# tinynumitronboard-extended_iv6.net
KiCad netlist of a schematic drawn in EAGLE
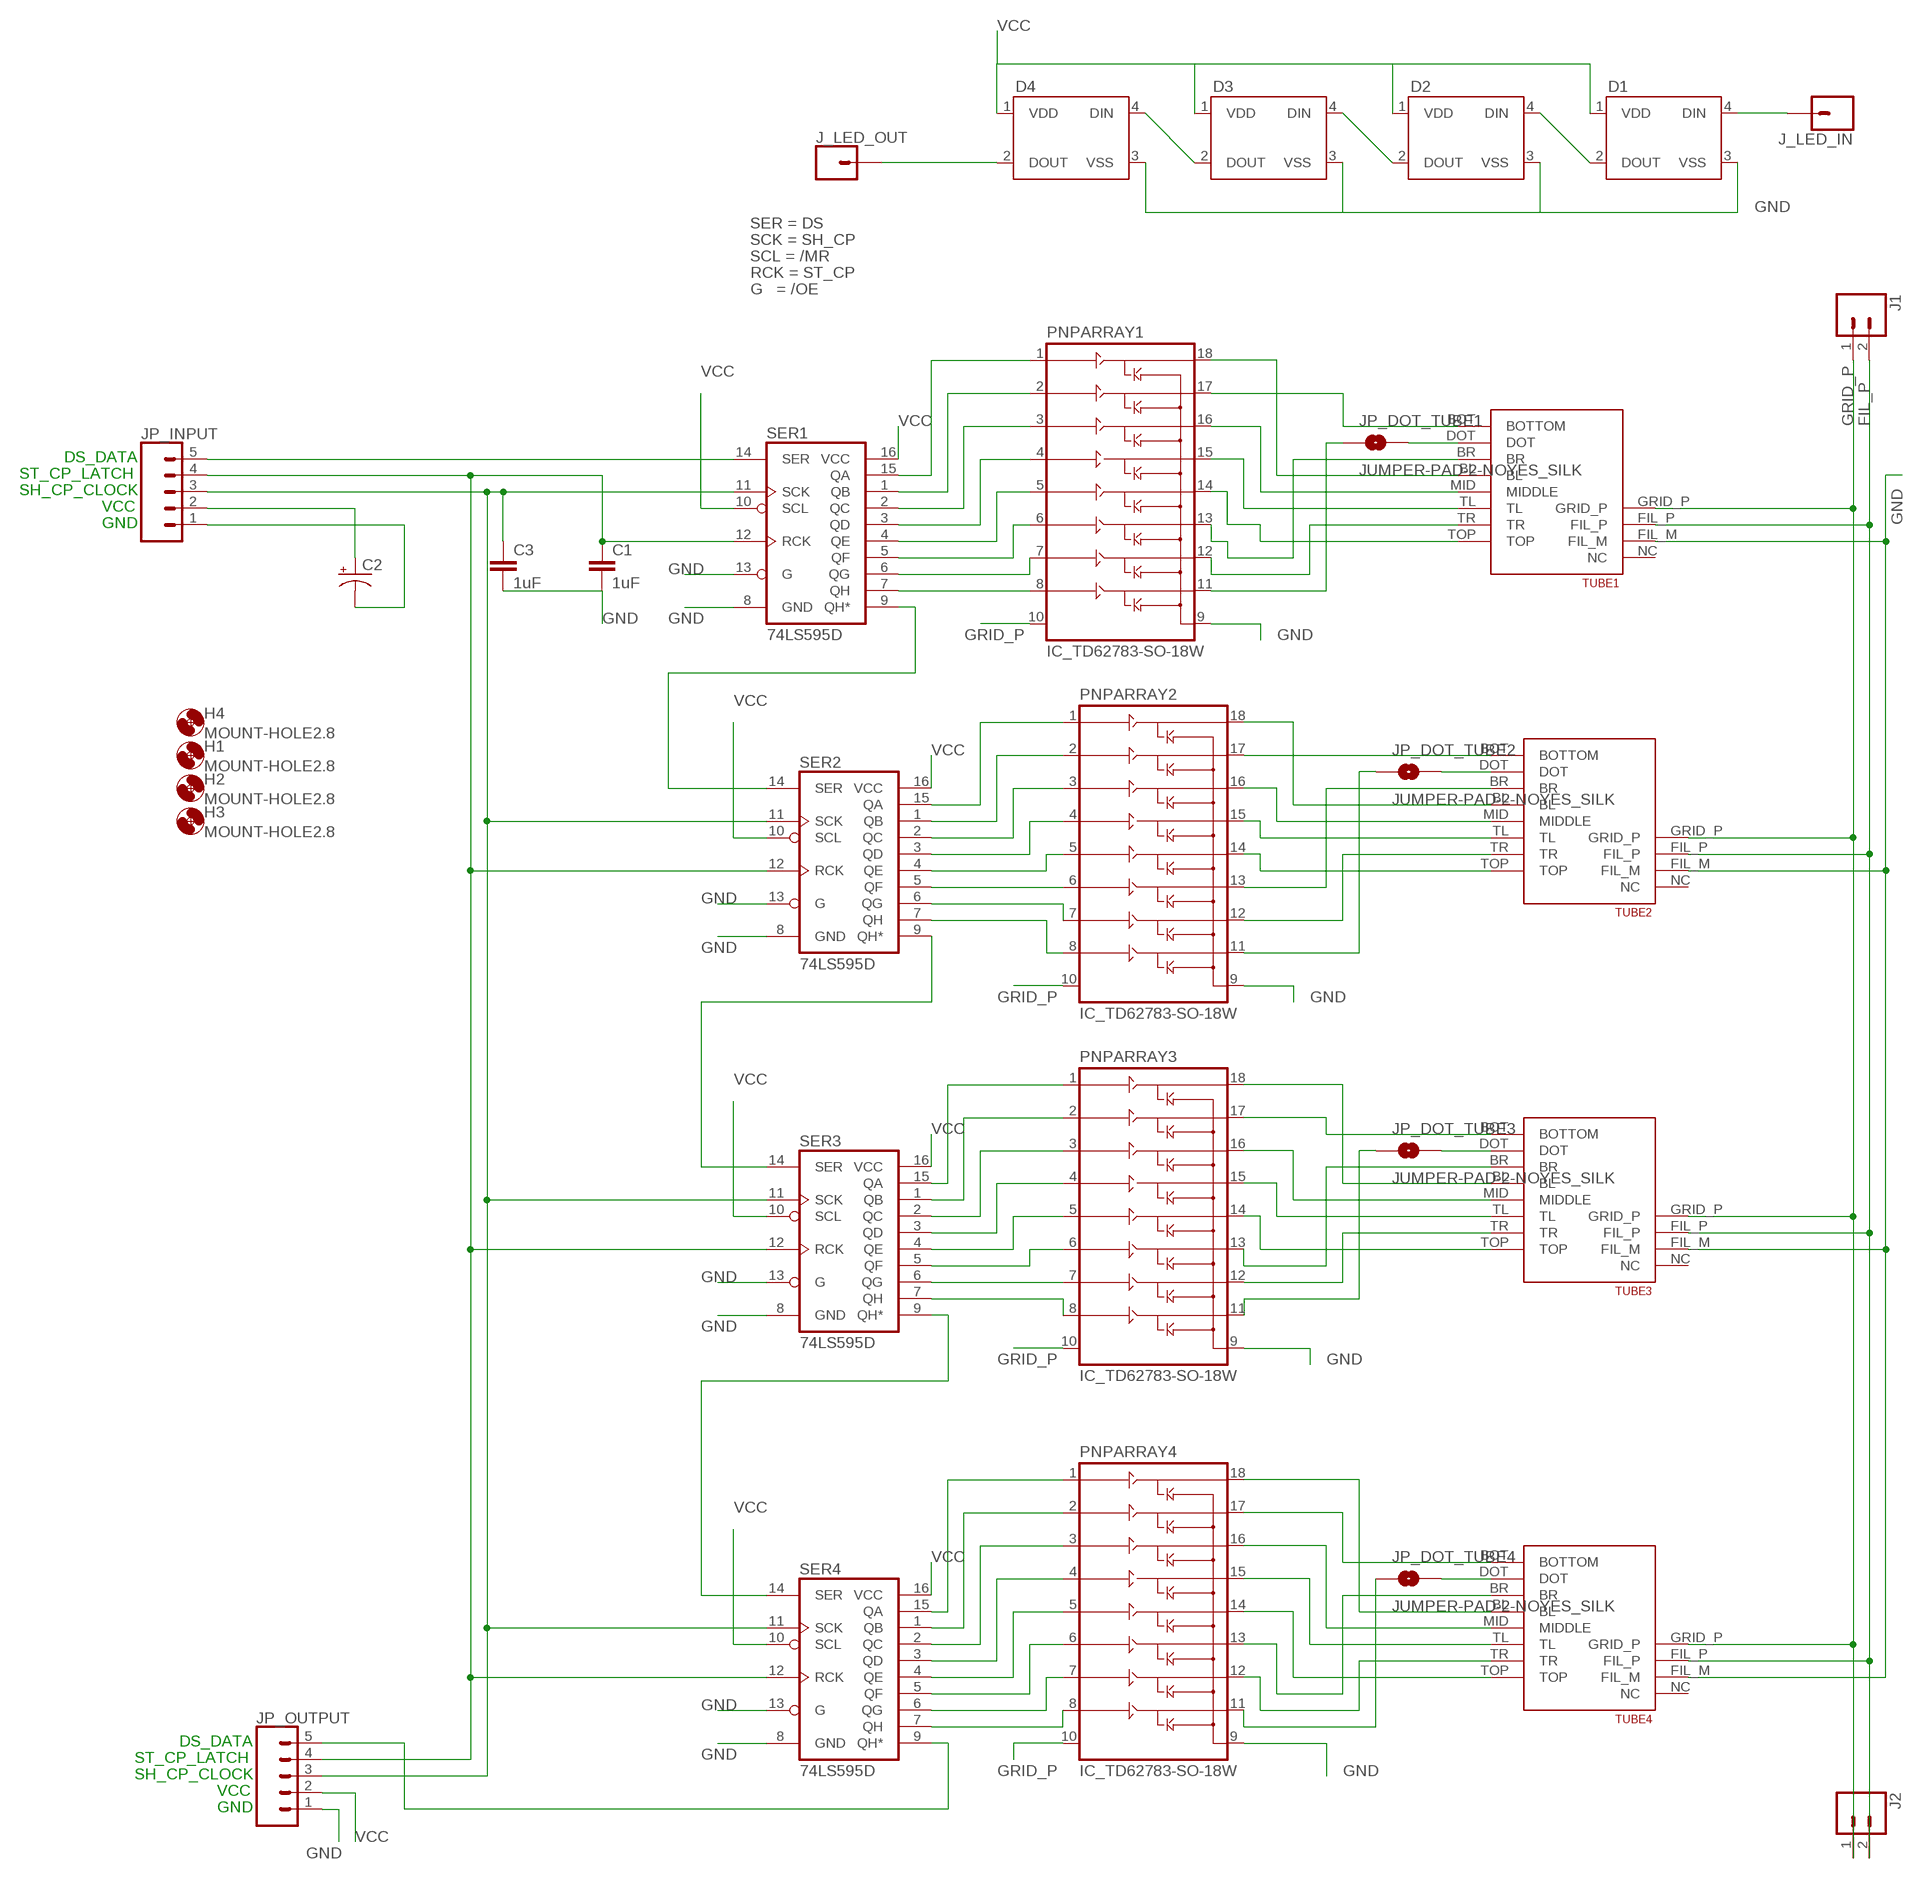
[diagram p0: schematic, sheet 1]

(export (version "E")
  (design (tool "Eeschema 10.0.6"))
  (components
    (comp (ref "C1")
      (value "1uF")
      (footprint "eagle-import:C1206")
      (libsource (lib "eagle-import") (part "C-EUC1206"))
    )
    (comp (ref "C2")
      (value "CAP_POLD")
      (footprint "eagle-import:PANASONIC_D")
      (libsource (lib "eagle-import") (part "CAP_POLD"))
    )
    (comp (ref "C3")
      (value "1uF")
      (footprint "eagle-import:C1206")
      (libsource (lib "eagle-import") (part "C-EUC1206"))
    )
    (comp (ref "D1")
      (value "WS2812B")
      (footprint "eagle-import:WS2812B")
      (libsource (lib "eagle-import") (part "WS2812B"))
    )
    (comp (ref "D2")
      (value "WS2812B")
      (footprint "eagle-import:WS2812B")
      (libsource (lib "eagle-import") (part "WS2812B"))
    )
    (comp (ref "D3")
      (value "WS2812B")
      (footprint "eagle-import:WS2812B")
      (libsource (lib "eagle-import") (part "WS2812B"))
    )
    (comp (ref "D4")
      (value "WS2812B")
      (footprint "eagle-import:WS2812B")
      (libsource (lib "eagle-import") (part "WS2812B"))
    )
    (comp (ref "H1")
      (value "MOUNT-HOLE2.8")
      (footprint "eagle-import:2,8")
      (libsource (lib "eagle-import") (part "MOUNT-HOLE2.8"))
    )
    (comp (ref "H2")
      (value "MOUNT-HOLE2.8")
      (footprint "eagle-import:2,8")
      (libsource (lib "eagle-import") (part "MOUNT-HOLE2.8"))
    )
    (comp (ref "H3")
      (value "MOUNT-HOLE2.8")
      (footprint "eagle-import:2,8")
      (libsource (lib "eagle-import") (part "MOUNT-HOLE2.8"))
    )
    (comp (ref "H4")
      (value "MOUNT-HOLE2.8")
      (footprint "eagle-import:2,8")
      (libsource (lib "eagle-import") (part "MOUNT-HOLE2.8"))
    )
    (comp (ref "J1")
      (value "CONN_021X02_NO_SILK")
      (footprint "eagle-import:1X02_NO_SILK")
      (libsource (lib "eagle-import") (part "CONN_021X02_NO_SILK"))
    )
    (comp (ref "J2")
      (value "CONN_021X02_NO_SILK")
      (footprint "eagle-import:1X02_NO_SILK")
      (libsource (lib "eagle-import") (part "CONN_021X02_NO_SILK"))
    )
    (comp (ref "JP_DOT_TUBE1")
      (value "JUMPER-PAD-2-NOYES_SILK")
      (footprint "eagle-import:PAD-JUMPER-2-NO_YES_SILK")
      (libsource (lib "eagle-import") (part "JUMPER-PAD-2-NOYES_SILK"))
    )
    (comp (ref "JP_DOT_TUBE2")
      (value "JUMPER-PAD-2-NOYES_SILK")
      (footprint "eagle-import:PAD-JUMPER-2-NO_YES_SILK")
      (libsource (lib "eagle-import") (part "JUMPER-PAD-2-NOYES_SILK"))
    )
    (comp (ref "JP_DOT_TUBE3")
      (value "JUMPER-PAD-2-NOYES_SILK")
      (footprint "eagle-import:PAD-JUMPER-2-NO_YES_SILK")
      (libsource (lib "eagle-import") (part "JUMPER-PAD-2-NOYES_SILK"))
    )
    (comp (ref "JP_DOT_TUBE4")
      (value "JUMPER-PAD-2-NOYES_SILK")
      (footprint "eagle-import:PAD-JUMPER-2-NO_YES_SILK")
      (libsource (lib "eagle-import") (part "JUMPER-PAD-2-NOYES_SILK"))
    )
    (comp (ref "JP_INPUT")
      (value "CONN_05NO_SILK")
      (footprint "eagle-import:1X05_NO_SILK")
      (libsource (lib "eagle-import") (part "CONN_05NO_SILK"))
    )
    (comp (ref "JP_OUTPUT")
      (value "CONN_05NO_SILK")
      (footprint "eagle-import:1X05_NO_SILK")
      (libsource (lib "eagle-import") (part "CONN_05NO_SILK"))
    )
    (comp (ref "J_LED_IN")
      (value "CONN_01")
      (footprint "eagle-import:1X01")
      (libsource (lib "eagle-import") (part "CONN_01"))
    )
    (comp (ref "J_LED_OUT")
      (value "CONN_01")
      (footprint "eagle-import:1X01")
      (libsource (lib "eagle-import") (part "CONN_01"))
    )
    (comp (ref "PNPARRAY1")
      (value "IC_TD62783-SO-18W")
      (footprint "eagle-import:SO-18L")
      (libsource (lib "eagle-import") (part "IC_TD62783-SO-18W"))
    )
    (comp (ref "PNPARRAY2")
      (value "IC_TD62783-SO-18W")
      (footprint "eagle-import:SO-18L")
      (libsource (lib "eagle-import") (part "IC_TD62783-SO-18W"))
    )
    (comp (ref "PNPARRAY3")
      (value "IC_TD62783-SO-18W")
      (footprint "eagle-import:SO-18L")
      (libsource (lib "eagle-import") (part "IC_TD62783-SO-18W"))
    )
    (comp (ref "PNPARRAY4")
      (value "IC_TD62783-SO-18W")
      (footprint "eagle-import:SO-18L")
      (libsource (lib "eagle-import") (part "IC_TD62783-SO-18W"))
    )
    (comp (ref "SER1")
      (value "74LS595D")
      (footprint "eagle-import:SO16")
      (libsource (lib "eagle-import") (part "74595DLS"))
    )
    (comp (ref "SER2")
      (value "74LS595D")
      (footprint "eagle-import:SO16")
      (libsource (lib "eagle-import") (part "74595DLS"))
    )
    (comp (ref "SER3")
      (value "74LS595D")
      (footprint "eagle-import:SO16")
      (libsource (lib "eagle-import") (part "74595DLS"))
    )
    (comp (ref "SER4")
      (value "74LS595D")
      (footprint "eagle-import:SO16")
      (libsource (lib "eagle-import") (part "74595DLS"))
    )
    (comp (ref "TUBE1")
      (value "IV6_NUMITRONLARGE")
      (footprint "eagle-import:IV6_NUMITRON_PAC_LARGE")
      (libsource (lib "eagle-import") (part "IV6_NUMITRONLARGE"))
    )
    (comp (ref "TUBE2")
      (value "IV6_NUMITRONLARGE")
      (footprint "eagle-import:IV6_NUMITRON_PAC_LARGE")
      (libsource (lib "eagle-import") (part "IV6_NUMITRONLARGE"))
    )
    (comp (ref "TUBE3")
      (value "IV6_NUMITRONLARGE")
      (footprint "eagle-import:IV6_NUMITRON_PAC_LARGE")
      (libsource (lib "eagle-import") (part "IV6_NUMITRONLARGE"))
    )
    (comp (ref "TUBE4")
      (value "IV6_NUMITRONLARGE")
      (footprint "eagle-import:IV6_NUMITRON_PAC_LARGE")
      (libsource (lib "eagle-import") (part "IV6_NUMITRONLARGE"))
    )
  )
  (nets
    (net (code "1") (name "/FIL_P") (class "Default")
      (node (ref "J1") (pin "2") (pinfunction "2_2") (pintype "passive"))
      (node (ref "J2") (pin "2") (pinfunction "2_2") (pintype "passive"))
      (node (ref "TUBE1") (pin "FIL_P") (pinfunction "FIL_P_FIL_P") (pintype "bidirectional"))
      (node (ref "TUBE2") (pin "FIL_P") (pinfunction "FIL_P_FIL_P") (pintype "bidirectional"))
      (node (ref "TUBE3") (pin "FIL_P") (pinfunction "FIL_P_FIL_P") (pintype "bidirectional"))
      (node (ref "TUBE4") (pin "FIL_P") (pinfunction "FIL_P_FIL_P") (pintype "bidirectional"))
    )
    (net (code "2") (name "/GND") (class "Default")
      (node (ref "C1") (pin "2") (pinfunction "2_2") (pintype "passive"))
      (node (ref "C2") (pin "-") (pinfunction "-_-") (pintype "passive"))
      (node (ref "C3") (pin "2") (pinfunction "2_2") (pintype "passive"))
      (node (ref "D1") (pin "3") (pinfunction "VSS_3") (pintype "power_in"))
      (node (ref "D2") (pin "3") (pinfunction "VSS_3") (pintype "power_in"))
      (node (ref "D3") (pin "3") (pinfunction "VSS_3") (pintype "power_in"))
      (node (ref "D4") (pin "3") (pinfunction "VSS_3") (pintype "power_in"))
      (node (ref "JP_INPUT") (pin "1") (pinfunction "1_1") (pintype "passive"))
      (node (ref "JP_OUTPUT") (pin "1") (pinfunction "1_1") (pintype "passive"))
      (node (ref "PNPARRAY1") (pin "9") (pinfunction "GND_9") (pintype "power_in"))
      (node (ref "PNPARRAY2") (pin "9") (pinfunction "GND_9") (pintype "power_in"))
      (node (ref "PNPARRAY3") (pin "9") (pinfunction "GND_9") (pintype "power_in"))
      (node (ref "PNPARRAY4") (pin "9") (pinfunction "GND_9") (pintype "power_in"))
      (node (ref "SER1") (pin "13") (pinfunction "G_13") (pintype "input"))
      (node (ref "SER1") (pin "8") (pinfunction "GND_8") (pintype "power_in"))
      (node (ref "SER2") (pin "13") (pinfunction "G_13") (pintype "input"))
      (node (ref "SER2") (pin "8") (pinfunction "GND_8") (pintype "power_in"))
      (node (ref "SER3") (pin "13") (pinfunction "G_13") (pintype "input"))
      (node (ref "SER3") (pin "8") (pinfunction "GND_8") (pintype "power_in"))
      (node (ref "SER4") (pin "13") (pinfunction "G_13") (pintype "input"))
      (node (ref "SER4") (pin "8") (pinfunction "GND_8") (pintype "power_in"))
      (node (ref "TUBE1") (pin "FIL_M") (pinfunction "FIL_M_FIL_M") (pintype "bidirectional"))
      (node (ref "TUBE2") (pin "FIL_M") (pinfunction "FIL_M_FIL_M") (pintype "bidirectional"))
      (node (ref "TUBE3") (pin "FIL_M") (pinfunction "FIL_M_FIL_M") (pintype "bidirectional"))
      (node (ref "TUBE4") (pin "FIL_M") (pinfunction "FIL_M_FIL_M") (pintype "bidirectional"))
    )
    (net (code "3") (name "/GRID_P") (class "Default")
      (node (ref "J1") (pin "1") (pinfunction "1_1") (pintype "passive"))
      (node (ref "J2") (pin "1") (pinfunction "1_1") (pintype "passive"))
      (node (ref "PNPARRAY1") (pin "10") (pinfunction "VS_10") (pintype "power_in"))
      (node (ref "PNPARRAY2") (pin "10") (pinfunction "VS_10") (pintype "power_in"))
      (node (ref "PNPARRAY3") (pin "10") (pinfunction "VS_10") (pintype "power_in"))
      (node (ref "PNPARRAY4") (pin "10") (pinfunction "VS_10") (pintype "power_in"))
      (node (ref "TUBE1") (pin "GRID_P") (pinfunction "GRID_P_GRID_P") (pintype "bidirectional"))
      (node (ref "TUBE2") (pin "GRID_P") (pinfunction "GRID_P_GRID_P") (pintype "bidirectional"))
      (node (ref "TUBE3") (pin "GRID_P") (pinfunction "GRID_P_GRID_P") (pintype "bidirectional"))
      (node (ref "TUBE4") (pin "GRID_P") (pinfunction "GRID_P_GRID_P") (pintype "bidirectional"))
    )
    (net (code "4") (name "/VCC") (class "Default")
      (node (ref "C2") (pin "+") (pinfunction "+_+") (pintype "passive"))
      (node (ref "D1") (pin "1") (pinfunction "VDD_1") (pintype "power_in"))
      (node (ref "D2") (pin "1") (pinfunction "VDD_1") (pintype "power_in"))
      (node (ref "D3") (pin "1") (pinfunction "VDD_1") (pintype "power_in"))
      (node (ref "D4") (pin "1") (pinfunction "VDD_1") (pintype "power_in"))
      (node (ref "JP_INPUT") (pin "2") (pinfunction "2_2") (pintype "passive"))
      (node (ref "JP_OUTPUT") (pin "2") (pinfunction "2_2") (pintype "passive"))
      (node (ref "SER1") (pin "10") (pinfunction "SCL_10") (pintype "input"))
      (node (ref "SER1") (pin "16") (pinfunction "VCC_16") (pintype "power_in"))
      (node (ref "SER2") (pin "10") (pinfunction "SCL_10") (pintype "input"))
      (node (ref "SER2") (pin "16") (pinfunction "VCC_16") (pintype "power_in"))
      (node (ref "SER3") (pin "10") (pinfunction "SCL_10") (pintype "input"))
      (node (ref "SER3") (pin "16") (pinfunction "VCC_16") (pintype "power_in"))
      (node (ref "SER4") (pin "10") (pinfunction "SCL_10") (pintype "input"))
      (node (ref "SER4") (pin "16") (pinfunction "VCC_16") (pintype "power_in"))
    )
    (net (code "5") (name "Net-(D1-DIN)") (class "Default")
      (node (ref "D1") (pin "4") (pinfunction "DIN_4") (pintype "input"))
      (node (ref "J_LED_IN") (pin "1") (pinfunction "1_1") (pintype "passive"))
    )
    (net (code "6") (name "Net-(D1-DOUT)") (class "Default")
      (node (ref "D1") (pin "2") (pinfunction "DOUT_2") (pintype "output"))
      (node (ref "D2") (pin "4") (pinfunction "DIN_4") (pintype "input"))
    )
    (net (code "7") (name "Net-(D2-DOUT)") (class "Default")
      (node (ref "D2") (pin "2") (pinfunction "DOUT_2") (pintype "output"))
      (node (ref "D3") (pin "4") (pinfunction "DIN_4") (pintype "input"))
    )
    (net (code "8") (name "Net-(D3-DOUT)") (class "Default")
      (node (ref "D3") (pin "2") (pinfunction "DOUT_2") (pintype "output"))
      (node (ref "D4") (pin "4") (pinfunction "DIN_4") (pintype "input"))
    )
    (net (code "9") (name "Net-(D4-DOUT)") (class "Default")
      (node (ref "D4") (pin "2") (pinfunction "DOUT_2") (pintype "output"))
      (node (ref "J_LED_OUT") (pin "1") (pinfunction "1_1") (pintype "passive"))
    )
    (net (code "10") (name "Net-(JP_DOT_TUBE1-Pad2)") (class "Default")
      (node (ref "JP_DOT_TUBE1") (pin "2") (pinfunction "2_2") (pintype "passive"))
      (node (ref "TUBE1") (pin "DOT") (pinfunction "DOT_DOT") (pintype "bidirectional"))
    )
    (net (code "11") (name "Net-(JP_DOT_TUBE2-Pad2)") (class "Default")
      (node (ref "JP_DOT_TUBE2") (pin "2") (pinfunction "2_2") (pintype "passive"))
      (node (ref "TUBE2") (pin "DOT") (pinfunction "DOT_DOT") (pintype "bidirectional"))
    )
    (net (code "12") (name "Net-(JP_DOT_TUBE3-Pad2)") (class "Default")
      (node (ref "JP_DOT_TUBE3") (pin "2") (pinfunction "2_2") (pintype "passive"))
      (node (ref "TUBE3") (pin "DOT") (pinfunction "DOT_DOT") (pintype "bidirectional"))
    )
    (net (code "13") (name "Net-(JP_DOT_TUBE4-Pad2)") (class "Default")
      (node (ref "JP_DOT_TUBE4") (pin "2") (pinfunction "2_2") (pintype "passive"))
      (node (ref "TUBE4") (pin "DOT") (pinfunction "DOT_DOT") (pintype "bidirectional"))
    )
    (net (code "14") (name "Net-(PNPARRAY1-IN1)") (class "Default")
      (node (ref "PNPARRAY1") (pin "1") (pinfunction "IN1_1") (pintype "input"))
      (node (ref "SER1") (pin "15") (pinfunction "QA_15") (pintype "tri_state"))
    )
    (net (code "15") (name "Net-(PNPARRAY1-IN2)") (class "Default")
      (node (ref "PNPARRAY1") (pin "2") (pinfunction "IN2_2") (pintype "input"))
      (node (ref "SER1") (pin "1") (pinfunction "QB_1") (pintype "tri_state"))
    )
    (net (code "16") (name "Net-(PNPARRAY1-IN3)") (class "Default")
      (node (ref "PNPARRAY1") (pin "3") (pinfunction "IN3_3") (pintype "input"))
      (node (ref "SER1") (pin "2") (pinfunction "QC_2") (pintype "tri_state"))
    )
    (net (code "17") (name "Net-(PNPARRAY1-IN4)") (class "Default")
      (node (ref "PNPARRAY1") (pin "4") (pinfunction "IN4_4") (pintype "input"))
      (node (ref "SER1") (pin "3") (pinfunction "QD_3") (pintype "tri_state"))
    )
    (net (code "18") (name "Net-(PNPARRAY1-IN5)") (class "Default")
      (node (ref "PNPARRAY1") (pin "5") (pinfunction "IN5_5") (pintype "input"))
      (node (ref "SER1") (pin "4") (pinfunction "QE_4") (pintype "tri_state"))
    )
    (net (code "19") (name "Net-(PNPARRAY1-IN6)") (class "Default")
      (node (ref "PNPARRAY1") (pin "6") (pinfunction "IN6_6") (pintype "input"))
      (node (ref "SER1") (pin "5") (pinfunction "QF_5") (pintype "tri_state"))
    )
    (net (code "20") (name "Net-(PNPARRAY1-IN7)") (class "Default")
      (node (ref "PNPARRAY1") (pin "7") (pinfunction "IN7_7") (pintype "input"))
      (node (ref "SER1") (pin "6") (pinfunction "QG_6") (pintype "tri_state"))
    )
    (net (code "21") (name "Net-(PNPARRAY1-IN8)") (class "Default")
      (node (ref "PNPARRAY1") (pin "8") (pinfunction "IN8_8") (pintype "input"))
      (node (ref "SER1") (pin "7") (pinfunction "QH_7") (pintype "tri_state"))
    )
    (net (code "22") (name "Net-(PNPARRAY1-OUT1)") (class "Default")
      (node (ref "PNPARRAY1") (pin "18") (pinfunction "OUT1_18") (pintype "output"))
      (node (ref "TUBE1") (pin "BL") (pinfunction "BL_BL") (pintype "bidirectional"))
    )
    (net (code "23") (name "Net-(PNPARRAY1-OUT2)") (class "Default")
      (node (ref "PNPARRAY1") (pin "17") (pinfunction "OUT2_17") (pintype "output"))
      (node (ref "TUBE1") (pin "BOT") (pinfunction "BOTTOM_BOT") (pintype "bidirectional"))
    )
    (net (code "24") (name "Net-(PNPARRAY1-OUT3)") (class "Default")
      (node (ref "PNPARRAY1") (pin "16") (pinfunction "OUT3_16") (pintype "output"))
      (node (ref "TUBE1") (pin "MID") (pinfunction "MIDDLE_MID") (pintype "bidirectional"))
    )
    (net (code "25") (name "Net-(PNPARRAY1-OUT4)") (class "Default")
      (node (ref "PNPARRAY1") (pin "15") (pinfunction "OUT4_15") (pintype "output"))
      (node (ref "TUBE1") (pin "TL") (pinfunction "TL_TL") (pintype "bidirectional"))
    )
    (net (code "26") (name "Net-(PNPARRAY1-OUT5)") (class "Default")
      (node (ref "PNPARRAY1") (pin "14") (pinfunction "OUT5_14") (pintype "output"))
      (node (ref "TUBE1") (pin "TOP") (pinfunction "TOP_TOP") (pintype "bidirectional"))
    )
    (net (code "27") (name "Net-(PNPARRAY1-OUT6)") (class "Default")
      (node (ref "PNPARRAY1") (pin "13") (pinfunction "OUT6_13") (pintype "output"))
      (node (ref "TUBE1") (pin "BR") (pinfunction "BR_BR") (pintype "bidirectional"))
    )
    (net (code "28") (name "Net-(PNPARRAY1-OUT7)") (class "Default")
      (node (ref "PNPARRAY1") (pin "12") (pinfunction "OUT7_12") (pintype "output"))
      (node (ref "TUBE1") (pin "TR") (pinfunction "TR_TR") (pintype "bidirectional"))
    )
    (net (code "29") (name "Net-(PNPARRAY1-OUT8)") (class "Default")
      (node (ref "JP_DOT_TUBE1") (pin "1") (pinfunction "1_1") (pintype "passive"))
      (node (ref "PNPARRAY1") (pin "11") (pinfunction "OUT8_11") (pintype "output"))
    )
    (net (code "30") (name "Net-(PNPARRAY2-IN1)") (class "Default")
      (node (ref "PNPARRAY2") (pin "1") (pinfunction "IN1_1") (pintype "input"))
      (node (ref "SER2") (pin "15") (pinfunction "QA_15") (pintype "tri_state"))
    )
    (net (code "31") (name "Net-(PNPARRAY2-IN2)") (class "Default")
      (node (ref "PNPARRAY2") (pin "2") (pinfunction "IN2_2") (pintype "input"))
      (node (ref "SER2") (pin "1") (pinfunction "QB_1") (pintype "tri_state"))
    )
    (net (code "32") (name "Net-(PNPARRAY2-IN3)") (class "Default")
      (node (ref "PNPARRAY2") (pin "3") (pinfunction "IN3_3") (pintype "input"))
      (node (ref "SER2") (pin "2") (pinfunction "QC_2") (pintype "tri_state"))
    )
    (net (code "33") (name "Net-(PNPARRAY2-IN4)") (class "Default")
      (node (ref "PNPARRAY2") (pin "4") (pinfunction "IN4_4") (pintype "input"))
      (node (ref "SER2") (pin "3") (pinfunction "QD_3") (pintype "tri_state"))
    )
    (net (code "34") (name "Net-(PNPARRAY2-IN5)") (class "Default")
      (node (ref "PNPARRAY2") (pin "5") (pinfunction "IN5_5") (pintype "input"))
      (node (ref "SER2") (pin "4") (pinfunction "QE_4") (pintype "tri_state"))
    )
    (net (code "35") (name "Net-(PNPARRAY2-IN6)") (class "Default")
      (node (ref "PNPARRAY2") (pin "6") (pinfunction "IN6_6") (pintype "input"))
      (node (ref "SER2") (pin "5") (pinfunction "QF_5") (pintype "tri_state"))
    )
    (net (code "36") (name "Net-(PNPARRAY2-IN7)") (class "Default")
      (node (ref "PNPARRAY2") (pin "7") (pinfunction "IN7_7") (pintype "input"))
      (node (ref "SER2") (pin "6") (pinfunction "QG_6") (pintype "tri_state"))
    )
    (net (code "37") (name "Net-(PNPARRAY2-IN8)") (class "Default")
      (node (ref "PNPARRAY2") (pin "8") (pinfunction "IN8_8") (pintype "input"))
      (node (ref "SER2") (pin "7") (pinfunction "QH_7") (pintype "tri_state"))
    )
    (net (code "38") (name "Net-(PNPARRAY2-OUT1)") (class "Default")
      (node (ref "PNPARRAY2") (pin "18") (pinfunction "OUT1_18") (pintype "output"))
      (node (ref "TUBE2") (pin "BL") (pinfunction "BL_BL") (pintype "bidirectional"))
    )
    (net (code "39") (name "Net-(PNPARRAY2-OUT2)") (class "Default")
      (node (ref "PNPARRAY2") (pin "17") (pinfunction "OUT2_17") (pintype "output"))
      (node (ref "TUBE2") (pin "BOT") (pinfunction "BOTTOM_BOT") (pintype "bidirectional"))
    )
    (net (code "40") (name "Net-(PNPARRAY2-OUT3)") (class "Default")
      (node (ref "PNPARRAY2") (pin "16") (pinfunction "OUT3_16") (pintype "output"))
      (node (ref "TUBE2") (pin "MID") (pinfunction "MIDDLE_MID") (pintype "bidirectional"))
    )
    (net (code "41") (name "Net-(PNPARRAY2-OUT4)") (class "Default")
      (node (ref "PNPARRAY2") (pin "15") (pinfunction "OUT4_15") (pintype "output"))
      (node (ref "TUBE2") (pin "TL") (pinfunction "TL_TL") (pintype "bidirectional"))
    )
    (net (code "42") (name "Net-(PNPARRAY2-OUT5)") (class "Default")
      (node (ref "PNPARRAY2") (pin "14") (pinfunction "OUT5_14") (pintype "output"))
      (node (ref "TUBE2") (pin "TOP") (pinfunction "TOP_TOP") (pintype "bidirectional"))
    )
    (net (code "43") (name "Net-(PNPARRAY2-OUT6)") (class "Default")
      (node (ref "PNPARRAY2") (pin "13") (pinfunction "OUT6_13") (pintype "output"))
      (node (ref "TUBE2") (pin "BR") (pinfunction "BR_BR") (pintype "bidirectional"))
    )
    (net (code "44") (name "Net-(PNPARRAY2-OUT7)") (class "Default")
      (node (ref "PNPARRAY2") (pin "12") (pinfunction "OUT7_12") (pintype "output"))
      (node (ref "TUBE2") (pin "TR") (pinfunction "TR_TR") (pintype "bidirectional"))
    )
    (net (code "45") (name "Net-(PNPARRAY2-OUT8)") (class "Default")
      (node (ref "JP_DOT_TUBE2") (pin "1") (pinfunction "1_1") (pintype "passive"))
      (node (ref "PNPARRAY2") (pin "11") (pinfunction "OUT8_11") (pintype "output"))
    )
    (net (code "46") (name "Net-(PNPARRAY3-IN1)") (class "Default")
      (node (ref "PNPARRAY3") (pin "1") (pinfunction "IN1_1") (pintype "input"))
      (node (ref "SER3") (pin "15") (pinfunction "QA_15") (pintype "tri_state"))
    )
    (net (code "47") (name "Net-(PNPARRAY3-IN2)") (class "Default")
      (node (ref "PNPARRAY3") (pin "2") (pinfunction "IN2_2") (pintype "input"))
      (node (ref "SER3") (pin "1") (pinfunction "QB_1") (pintype "tri_state"))
    )
    (net (code "48") (name "Net-(PNPARRAY3-IN3)") (class "Default")
      (node (ref "PNPARRAY3") (pin "3") (pinfunction "IN3_3") (pintype "input"))
      (node (ref "SER3") (pin "2") (pinfunction "QC_2") (pintype "tri_state"))
    )
    (net (code "49") (name "Net-(PNPARRAY3-IN4)") (class "Default")
      (node (ref "PNPARRAY3") (pin "4") (pinfunction "IN4_4") (pintype "input"))
      (node (ref "SER3") (pin "3") (pinfunction "QD_3") (pintype "tri_state"))
    )
    (net (code "50") (name "Net-(PNPARRAY3-IN5)") (class "Default")
      (node (ref "PNPARRAY3") (pin "5") (pinfunction "IN5_5") (pintype "input"))
      (node (ref "SER3") (pin "4") (pinfunction "QE_4") (pintype "tri_state"))
    )
    (net (code "51") (name "Net-(PNPARRAY3-IN6)") (class "Default")
      (node (ref "PNPARRAY3") (pin "6") (pinfunction "IN6_6") (pintype "input"))
      (node (ref "SER3") (pin "5") (pinfunction "QF_5") (pintype "tri_state"))
    )
    (net (code "52") (name "Net-(PNPARRAY3-IN7)") (class "Default")
      (node (ref "PNPARRAY3") (pin "7") (pinfunction "IN7_7") (pintype "input"))
      (node (ref "SER3") (pin "6") (pinfunction "QG_6") (pintype "tri_state"))
    )
    (net (code "53") (name "Net-(PNPARRAY3-IN8)") (class "Default")
      (node (ref "PNPARRAY3") (pin "8") (pinfunction "IN8_8") (pintype "input"))
      (node (ref "SER3") (pin "7") (pinfunction "QH_7") (pintype "tri_state"))
    )
    (net (code "54") (name "Net-(PNPARRAY3-OUT1)") (class "Default")
      (node (ref "PNPARRAY3") (pin "18") (pinfunction "OUT1_18") (pintype "output"))
      (node (ref "TUBE3") (pin "BL") (pinfunction "BL_BL") (pintype "bidirectional"))
    )
    (net (code "55") (name "Net-(PNPARRAY3-OUT2)") (class "Default")
      (node (ref "PNPARRAY3") (pin "17") (pinfunction "OUT2_17") (pintype "output"))
      (node (ref "TUBE3") (pin "BOT") (pinfunction "BOTTOM_BOT") (pintype "bidirectional"))
    )
    (net (code "56") (name "Net-(PNPARRAY3-OUT3)") (class "Default")
      (node (ref "PNPARRAY3") (pin "16") (pinfunction "OUT3_16") (pintype "output"))
      (node (ref "TUBE3") (pin "MID") (pinfunction "MIDDLE_MID") (pintype "bidirectional"))
    )
    (net (code "57") (name "Net-(PNPARRAY3-OUT4)") (class "Default")
      (node (ref "PNPARRAY3") (pin "15") (pinfunction "OUT4_15") (pintype "output"))
      (node (ref "TUBE3") (pin "TL") (pinfunction "TL_TL") (pintype "bidirectional"))
    )
    (net (code "58") (name "Net-(PNPARRAY3-OUT5)") (class "Default")
      (node (ref "PNPARRAY3") (pin "14") (pinfunction "OUT5_14") (pintype "output"))
      (node (ref "TUBE3") (pin "TOP") (pinfunction "TOP_TOP") (pintype "bidirectional"))
    )
    (net (code "59") (name "Net-(PNPARRAY3-OUT6)") (class "Default")
      (node (ref "PNPARRAY3") (pin "13") (pinfunction "OUT6_13") (pintype "output"))
      (node (ref "TUBE3") (pin "BR") (pinfunction "BR_BR") (pintype "bidirectional"))
    )
    (net (code "60") (name "Net-(PNPARRAY3-OUT7)") (class "Default")
      (node (ref "PNPARRAY3") (pin "12") (pinfunction "OUT7_12") (pintype "output"))
      (node (ref "TUBE3") (pin "TR") (pinfunction "TR_TR") (pintype "bidirectional"))
    )
    (net (code "61") (name "Net-(PNPARRAY3-OUT8)") (class "Default")
      (node (ref "JP_DOT_TUBE3") (pin "1") (pinfunction "1_1") (pintype "passive"))
      (node (ref "PNPARRAY3") (pin "11") (pinfunction "OUT8_11") (pintype "output"))
    )
    (net (code "62") (name "Net-(PNPARRAY4-IN1)") (class "Default")
      (node (ref "PNPARRAY4") (pin "1") (pinfunction "IN1_1") (pintype "input"))
      (node (ref "SER4") (pin "15") (pinfunction "QA_15") (pintype "tri_state"))
    )
    (net (code "63") (name "Net-(PNPARRAY4-IN2)") (class "Default")
      (node (ref "PNPARRAY4") (pin "2") (pinfunction "IN2_2") (pintype "input"))
      (node (ref "SER4") (pin "1") (pinfunction "QB_1") (pintype "tri_state"))
    )
    (net (code "64") (name "Net-(PNPARRAY4-IN3)") (class "Default")
      (node (ref "PNPARRAY4") (pin "3") (pinfunction "IN3_3") (pintype "input"))
      (node (ref "SER4") (pin "2") (pinfunction "QC_2") (pintype "tri_state"))
    )
    (net (code "65") (name "Net-(PNPARRAY4-IN4)") (class "Default")
      (node (ref "PNPARRAY4") (pin "4") (pinfunction "IN4_4") (pintype "input"))
      (node (ref "SER4") (pin "3") (pinfunction "QD_3") (pintype "tri_state"))
    )
    (net (code "66") (name "Net-(PNPARRAY4-IN5)") (class "Default")
      (node (ref "PNPARRAY4") (pin "5") (pinfunction "IN5_5") (pintype "input"))
      (node (ref "SER4") (pin "4") (pinfunction "QE_4") (pintype "tri_state"))
    )
    (net (code "67") (name "Net-(PNPARRAY4-IN6)") (class "Default")
      (node (ref "PNPARRAY4") (pin "6") (pinfunction "IN6_6") (pintype "input"))
      (node (ref "SER4") (pin "5") (pinfunction "QF_5") (pintype "tri_state"))
    )
    (net (code "68") (name "Net-(PNPARRAY4-IN7)") (class "Default")
      (node (ref "PNPARRAY4") (pin "7") (pinfunction "IN7_7") (pintype "input"))
      (node (ref "SER4") (pin "6") (pinfunction "QG_6") (pintype "tri_state"))
    )
    (net (code "69") (name "Net-(PNPARRAY4-IN8)") (class "Default")
      (node (ref "PNPARRAY4") (pin "8") (pinfunction "IN8_8") (pintype "input"))
      (node (ref "SER4") (pin "7") (pinfunction "QH_7") (pintype "tri_state"))
    )
    (net (code "70") (name "Net-(PNPARRAY4-OUT1)") (class "Default")
      (node (ref "PNPARRAY4") (pin "18") (pinfunction "OUT1_18") (pintype "output"))
      (node (ref "TUBE4") (pin "BL") (pinfunction "BL_BL") (pintype "bidirectional"))
    )
    (net (code "71") (name "Net-(PNPARRAY4-OUT2)") (class "Default")
      (node (ref "PNPARRAY4") (pin "17") (pinfunction "OUT2_17") (pintype "output"))
      (node (ref "TUBE4") (pin "BOT") (pinfunction "BOTTOM_BOT") (pintype "bidirectional"))
    )
    (net (code "72") (name "Net-(PNPARRAY4-OUT3)") (class "Default")
      (node (ref "PNPARRAY4") (pin "16") (pinfunction "OUT3_16") (pintype "output"))
      (node (ref "TUBE4") (pin "MID") (pinfunction "MIDDLE_MID") (pintype "bidirectional"))
    )
    (net (code "73") (name "Net-(PNPARRAY4-OUT4)") (class "Default")
      (node (ref "PNPARRAY4") (pin "15") (pinfunction "OUT4_15") (pintype "output"))
      (node (ref "TUBE4") (pin "TL") (pinfunction "TL_TL") (pintype "bidirectional"))
    )
    (net (code "74") (name "Net-(PNPARRAY4-OUT5)") (class "Default")
      (node (ref "PNPARRAY4") (pin "14") (pinfunction "OUT5_14") (pintype "output"))
      (node (ref "TUBE4") (pin "TOP") (pinfunction "TOP_TOP") (pintype "bidirectional"))
    )
    (net (code "75") (name "Net-(PNPARRAY4-OUT6)") (class "Default")
      (node (ref "PNPARRAY4") (pin "13") (pinfunction "OUT6_13") (pintype "output"))
      (node (ref "TUBE4") (pin "BR") (pinfunction "BR_BR") (pintype "bidirectional"))
    )
    (net (code "76") (name "Net-(PNPARRAY4-OUT7)") (class "Default")
      (node (ref "PNPARRAY4") (pin "12") (pinfunction "OUT7_12") (pintype "output"))
      (node (ref "TUBE4") (pin "TR") (pinfunction "TR_TR") (pintype "bidirectional"))
    )
    (net (code "77") (name "Net-(PNPARRAY4-OUT8)") (class "Default")
      (node (ref "JP_DOT_TUBE4") (pin "1") (pinfunction "1_1") (pintype "passive"))
      (node (ref "PNPARRAY4") (pin "11") (pinfunction "OUT8_11") (pintype "output"))
    )
    (net (code "78") (name "Net-(SER1-QH*)") (class "Default")
      (node (ref "SER1") (pin "9") (pinfunction "QH*_9") (pintype "tri_state"))
      (node (ref "SER2") (pin "14") (pinfunction "SER_14") (pintype "input"))
    )
    (net (code "79") (name "Net-(SER1-RCK)") (class "Default")
      (node (ref "C1") (pin "1") (pinfunction "1_1") (pintype "passive"))
      (node (ref "JP_INPUT") (pin "4") (pinfunction "4_4") (pintype "passive"))
      (node (ref "JP_OUTPUT") (pin "4") (pinfunction "4_4") (pintype "passive"))
      (node (ref "SER1") (pin "12") (pinfunction "RCK_12") (pintype "input"))
      (node (ref "SER2") (pin "12") (pinfunction "RCK_12") (pintype "input"))
      (node (ref "SER3") (pin "12") (pinfunction "RCK_12") (pintype "input"))
      (node (ref "SER4") (pin "12") (pinfunction "RCK_12") (pintype "input"))
    )
    (net (code "80") (name "Net-(SER1-SCK)") (class "Default")
      (node (ref "C3") (pin "1") (pinfunction "1_1") (pintype "passive"))
      (node (ref "JP_INPUT") (pin "3") (pinfunction "3_3") (pintype "passive"))
      (node (ref "JP_OUTPUT") (pin "3") (pinfunction "3_3") (pintype "passive"))
      (node (ref "SER1") (pin "11") (pinfunction "SCK_11") (pintype "input"))
      (node (ref "SER2") (pin "11") (pinfunction "SCK_11") (pintype "input"))
      (node (ref "SER3") (pin "11") (pinfunction "SCK_11") (pintype "input"))
      (node (ref "SER4") (pin "11") (pinfunction "SCK_11") (pintype "input"))
    )
    (net (code "81") (name "Net-(SER1-SER)") (class "Default")
      (node (ref "JP_INPUT") (pin "5") (pinfunction "5_5") (pintype "passive"))
      (node (ref "SER1") (pin "14") (pinfunction "SER_14") (pintype "input"))
    )
    (net (code "82") (name "Net-(SER2-QH*)") (class "Default")
      (node (ref "SER2") (pin "9") (pinfunction "QH*_9") (pintype "tri_state"))
      (node (ref "SER3") (pin "14") (pinfunction "SER_14") (pintype "input"))
    )
    (net (code "83") (name "Net-(SER3-QH*)") (class "Default")
      (node (ref "SER3") (pin "9") (pinfunction "QH*_9") (pintype "tri_state"))
      (node (ref "SER4") (pin "14") (pinfunction "SER_14") (pintype "input"))
    )
    (net (code "84") (name "Net-(SER4-QH*)") (class "Default")
      (node (ref "JP_OUTPUT") (pin "5") (pinfunction "5_5") (pintype "passive"))
      (node (ref "SER4") (pin "9") (pinfunction "QH*_9") (pintype "tri_state"))
    )
    (net (code "85") (name "unconnected-(TUBE1-PadNC)") (class "Default")
      (node (ref "TUBE1") (pin "NC") (pinfunction "NC_NC") (pintype "bidirectional"))
    )
    (net (code "86") (name "unconnected-(TUBE2-PadNC)") (class "Default")
      (node (ref "TUBE2") (pin "NC") (pinfunction "NC_NC") (pintype "bidirectional"))
    )
    (net (code "87") (name "unconnected-(TUBE3-PadNC)") (class "Default")
      (node (ref "TUBE3") (pin "NC") (pinfunction "NC_NC") (pintype "bidirectional"))
    )
    (net (code "88") (name "unconnected-(TUBE4-PadNC)") (class "Default")
      (node (ref "TUBE4") (pin "NC") (pinfunction "NC_NC") (pintype "bidirectional"))
    )
  )
)
